# 5_-BUTTONS_ILLUMINATION.net
KiCad netlist of a schematic drawn in Altium Designer
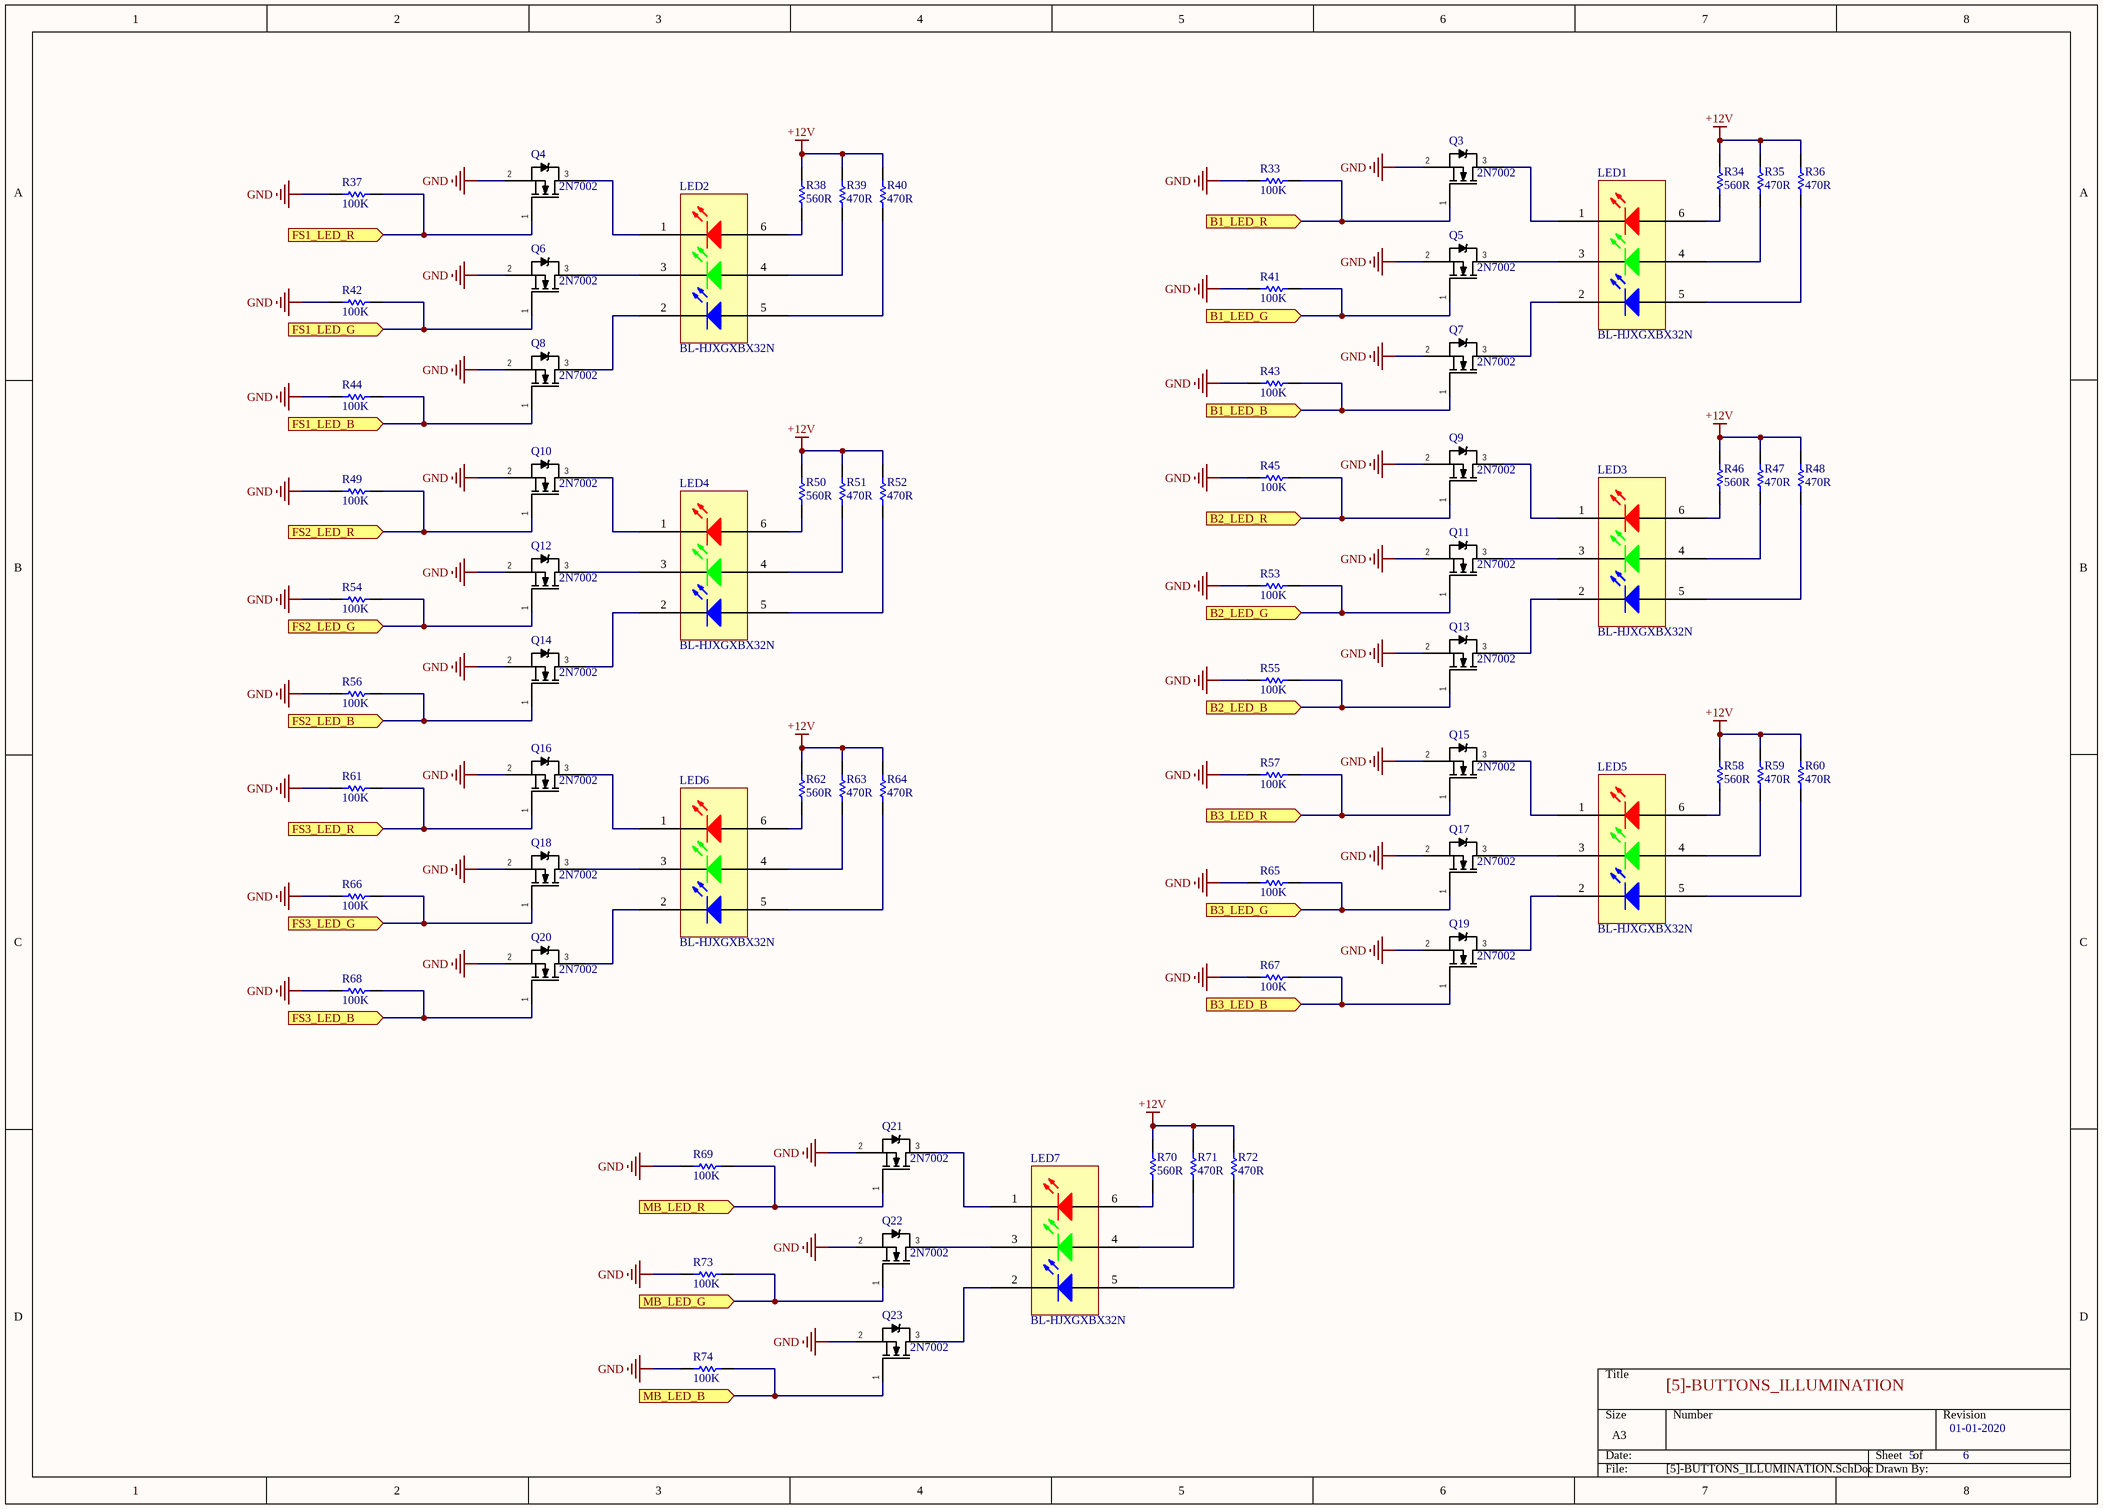
[diagram p0: [5]-BUTTONS_ILLUMINATION.SchDoc]

(export (version "E")
  (design (tool "Eeschema 10.0.6"))
  (components
    (comp (ref "LED1")
      (value "BL-HJXGXBX32N")
      (footprint "BL-HJXGXBX32N")
      (description "LED RGB 6PLCC SMD")
      (libsource (lib "bitsnio") (part "BL-HJXGXBX32N"))
    )
    (comp (ref "LED2")
      (value "BL-HJXGXBX32N")
      (footprint "BL-HJXGXBX32N")
      (description "LED RGB 6PLCC SMD")
      (libsource (lib "bitsnio") (part "BL-HJXGXBX32N"))
    )
    (comp (ref "LED3")
      (value "BL-HJXGXBX32N")
      (footprint "BL-HJXGXBX32N")
      (description "LED RGB 6PLCC SMD")
      (libsource (lib "bitsnio") (part "BL-HJXGXBX32N"))
    )
    (comp (ref "LED4")
      (value "BL-HJXGXBX32N")
      (footprint "BL-HJXGXBX32N")
      (description "LED RGB 6PLCC SMD")
      (libsource (lib "bitsnio") (part "BL-HJXGXBX32N"))
    )
    (comp (ref "LED5")
      (value "BL-HJXGXBX32N")
      (footprint "BL-HJXGXBX32N")
      (description "LED RGB 6PLCC SMD")
      (libsource (lib "bitsnio") (part "BL-HJXGXBX32N"))
    )
    (comp (ref "LED6")
      (value "BL-HJXGXBX32N")
      (footprint "BL-HJXGXBX32N")
      (description "LED RGB 6PLCC SMD")
      (libsource (lib "bitsnio") (part "BL-HJXGXBX32N"))
    )
    (comp (ref "LED7")
      (value "BL-HJXGXBX32N")
      (footprint "BL-HJXGXBX32N")
      (description "LED RGB 6PLCC SMD")
      (libsource (lib "bitsnio") (part "BL-HJXGXBX32N"))
    )
    (comp (ref "Q3")
      (value "2N7002")
      (footprint "SOT23-3N")
      (description "MOSFET N-CH 60V 115MA SOT-23")
      (fields (field (name "VOLTAGE") "60V"))
      (libsource (lib "bitsnio") (part "2N7002"))
    )
    (comp (ref "Q4")
      (value "2N7002")
      (footprint "SOT23-3N")
      (description "MOSFET N-CH 60V 115MA SOT-23")
      (fields (field (name "VOLTAGE") "60V"))
      (libsource (lib "bitsnio") (part "2N7002"))
    )
    (comp (ref "Q5")
      (value "2N7002")
      (footprint "SOT23-3N")
      (description "MOSFET N-CH 60V 115MA SOT-23")
      (fields (field (name "VOLTAGE") "60V"))
      (libsource (lib "bitsnio") (part "2N7002"))
    )
    (comp (ref "Q6")
      (value "2N7002")
      (footprint "SOT23-3N")
      (description "MOSFET N-CH 60V 115MA SOT-23")
      (fields (field (name "VOLTAGE") "60V"))
      (libsource (lib "bitsnio") (part "2N7002"))
    )
    (comp (ref "Q7")
      (value "2N7002")
      (footprint "SOT23-3N")
      (description "MOSFET N-CH 60V 115MA SOT-23")
      (fields (field (name "VOLTAGE") "60V"))
      (libsource (lib "bitsnio") (part "2N7002"))
    )
    (comp (ref "Q8")
      (value "2N7002")
      (footprint "SOT23-3N")
      (description "MOSFET N-CH 60V 115MA SOT-23")
      (fields (field (name "VOLTAGE") "60V"))
      (libsource (lib "bitsnio") (part "2N7002"))
    )
    (comp (ref "Q9")
      (value "2N7002")
      (footprint "SOT23-3N")
      (description "MOSFET N-CH 60V 115MA SOT-23")
      (fields (field (name "VOLTAGE") "60V"))
      (libsource (lib "bitsnio") (part "2N7002"))
    )
    (comp (ref "Q10")
      (value "2N7002")
      (footprint "SOT23-3N")
      (description "MOSFET N-CH 60V 115MA SOT-23")
      (fields (field (name "VOLTAGE") "60V"))
      (libsource (lib "bitsnio") (part "2N7002"))
    )
    (comp (ref "Q11")
      (value "2N7002")
      (footprint "SOT23-3N")
      (description "MOSFET N-CH 60V 115MA SOT-23")
      (fields (field (name "VOLTAGE") "60V"))
      (libsource (lib "bitsnio") (part "2N7002"))
    )
    (comp (ref "Q12")
      (value "2N7002")
      (footprint "SOT23-3N")
      (description "MOSFET N-CH 60V 115MA SOT-23")
      (fields (field (name "VOLTAGE") "60V"))
      (libsource (lib "bitsnio") (part "2N7002"))
    )
    (comp (ref "Q13")
      (value "2N7002")
      (footprint "SOT23-3N")
      (description "MOSFET N-CH 60V 115MA SOT-23")
      (fields (field (name "VOLTAGE") "60V"))
      (libsource (lib "bitsnio") (part "2N7002"))
    )
    (comp (ref "Q14")
      (value "2N7002")
      (footprint "SOT23-3N")
      (description "MOSFET N-CH 60V 115MA SOT-23")
      (fields (field (name "VOLTAGE") "60V"))
      (libsource (lib "bitsnio") (part "2N7002"))
    )
    (comp (ref "Q15")
      (value "2N7002")
      (footprint "SOT23-3N")
      (description "MOSFET N-CH 60V 115MA SOT-23")
      (fields (field (name "VOLTAGE") "60V"))
      (libsource (lib "bitsnio") (part "2N7002"))
    )
    (comp (ref "Q16")
      (value "2N7002")
      (footprint "SOT23-3N")
      (description "MOSFET N-CH 60V 115MA SOT-23")
      (fields (field (name "VOLTAGE") "60V"))
      (libsource (lib "bitsnio") (part "2N7002"))
    )
    (comp (ref "Q17")
      (value "2N7002")
      (footprint "SOT23-3N")
      (description "MOSFET N-CH 60V 115MA SOT-23")
      (fields (field (name "VOLTAGE") "60V"))
      (libsource (lib "bitsnio") (part "2N7002"))
    )
    (comp (ref "Q18")
      (value "2N7002")
      (footprint "SOT23-3N")
      (description "MOSFET N-CH 60V 115MA SOT-23")
      (fields (field (name "VOLTAGE") "60V"))
      (libsource (lib "bitsnio") (part "2N7002"))
    )
    (comp (ref "Q19")
      (value "2N7002")
      (footprint "SOT23-3N")
      (description "MOSFET N-CH 60V 115MA SOT-23")
      (fields (field (name "VOLTAGE") "60V"))
      (libsource (lib "bitsnio") (part "2N7002"))
    )
    (comp (ref "Q20")
      (value "2N7002")
      (footprint "SOT23-3N")
      (description "MOSFET N-CH 60V 115MA SOT-23")
      (fields (field (name "VOLTAGE") "60V"))
      (libsource (lib "bitsnio") (part "2N7002"))
    )
    (comp (ref "Q21")
      (value "2N7002")
      (footprint "SOT23-3N")
      (description "MOSFET N-CH 60V 115MA SOT-23")
      (fields (field (name "VOLTAGE") "60V"))
      (libsource (lib "bitsnio") (part "2N7002"))
    )
    (comp (ref "Q22")
      (value "2N7002")
      (footprint "SOT23-3N")
      (description "MOSFET N-CH 60V 115MA SOT-23")
      (fields (field (name "VOLTAGE") "60V"))
      (libsource (lib "bitsnio") (part "2N7002"))
    )
    (comp (ref "Q23")
      (value "2N7002")
      (footprint "SOT23-3N")
      (description "MOSFET N-CH 60V 115MA SOT-23")
      (fields (field (name "VOLTAGE") "60V"))
      (libsource (lib "bitsnio") (part "2N7002"))
    )
    (comp (ref "R33")
      (value "100K")
      (footprint "RESC1608N")
      (description "RES SMD 100K OHM 5% 1/4W 0603")
      (fields (field (name "TOLERANCE") "5%"))
      (libsource (lib "bitsnio") (part "ESR03EZPJ104"))
    )
    (comp (ref "R34")
      (value "560R")
      (footprint "RESC1608N")
      (description "RES SMD 560 OHM 5% 1/10W 0603")
      (fields (field (name "TOLERANCE") "5%"))
      (libsource (lib "bitsnio") (part "AC0603JR-07560RL"))
    )
    (comp (ref "R35")
      (value "470R")
      (footprint "RESC1608N")
      (description "RES SMD 470 OHM 5% 1/10W 0603")
      (fields (field (name "TOLERANCE") "5%"))
      (libsource (lib "bitsnio") (part "RMCF0603JT470R"))
    )
    (comp (ref "R36")
      (value "470R")
      (footprint "RESC1608N")
      (description "RES SMD 470 OHM 5% 1/10W 0603")
      (fields (field (name "TOLERANCE") "5%"))
      (libsource (lib "bitsnio") (part "RMCF0603JT470R"))
    )
    (comp (ref "R37")
      (value "100K")
      (footprint "RESC1608N")
      (description "RES SMD 100K OHM 5% 1/4W 0603")
      (fields (field (name "TOLERANCE") "5%"))
      (libsource (lib "bitsnio") (part "ESR03EZPJ104"))
    )
    (comp (ref "R38")
      (value "560R")
      (footprint "RESC1608N")
      (description "RES SMD 560 OHM 5% 1/10W 0603")
      (fields (field (name "TOLERANCE") "5%"))
      (libsource (lib "bitsnio") (part "AC0603JR-07560RL"))
    )
    (comp (ref "R39")
      (value "470R")
      (footprint "RESC1608N")
      (description "RES SMD 470 OHM 5% 1/10W 0603")
      (fields (field (name "TOLERANCE") "5%"))
      (libsource (lib "bitsnio") (part "RMCF0603JT470R"))
    )
    (comp (ref "R40")
      (value "470R")
      (footprint "RESC1608N")
      (description "RES SMD 470 OHM 5% 1/10W 0603")
      (fields (field (name "TOLERANCE") "5%"))
      (libsource (lib "bitsnio") (part "RMCF0603JT470R"))
    )
    (comp (ref "R41")
      (value "100K")
      (footprint "RESC1608N")
      (description "RES SMD 100K OHM 5% 1/4W 0603")
      (fields (field (name "TOLERANCE") "5%"))
      (libsource (lib "bitsnio") (part "ESR03EZPJ104"))
    )
    (comp (ref "R42")
      (value "100K")
      (footprint "RESC1608N")
      (description "RES SMD 100K OHM 5% 1/4W 0603")
      (fields (field (name "TOLERANCE") "5%"))
      (libsource (lib "bitsnio") (part "ESR03EZPJ104"))
    )
    (comp (ref "R43")
      (value "100K")
      (footprint "RESC1608N")
      (description "RES SMD 100K OHM 5% 1/4W 0603")
      (fields (field (name "TOLERANCE") "5%"))
      (libsource (lib "bitsnio") (part "ESR03EZPJ104"))
    )
    (comp (ref "R44")
      (value "100K")
      (footprint "RESC1608N")
      (description "RES SMD 100K OHM 5% 1/4W 0603")
      (fields (field (name "TOLERANCE") "5%"))
      (libsource (lib "bitsnio") (part "ESR03EZPJ104"))
    )
    (comp (ref "R45")
      (value "100K")
      (footprint "RESC1608N")
      (description "RES SMD 100K OHM 5% 1/4W 0603")
      (fields (field (name "TOLERANCE") "5%"))
      (libsource (lib "bitsnio") (part "ESR03EZPJ104"))
    )
    (comp (ref "R46")
      (value "560R")
      (footprint "RESC1608N")
      (description "RES SMD 560 OHM 5% 1/10W 0603")
      (fields (field (name "TOLERANCE") "5%"))
      (libsource (lib "bitsnio") (part "AC0603JR-07560RL"))
    )
    (comp (ref "R47")
      (value "470R")
      (footprint "RESC1608N")
      (description "RES SMD 470 OHM 5% 1/10W 0603")
      (fields (field (name "TOLERANCE") "5%"))
      (libsource (lib "bitsnio") (part "RMCF0603JT470R"))
    )
    (comp (ref "R48")
      (value "470R")
      (footprint "RESC1608N")
      (description "RES SMD 470 OHM 5% 1/10W 0603")
      (fields (field (name "TOLERANCE") "5%"))
      (libsource (lib "bitsnio") (part "RMCF0603JT470R"))
    )
    (comp (ref "R49")
      (value "100K")
      (footprint "RESC1608N")
      (description "RES SMD 100K OHM 5% 1/4W 0603")
      (fields (field (name "TOLERANCE") "5%"))
      (libsource (lib "bitsnio") (part "ESR03EZPJ104"))
    )
    (comp (ref "R50")
      (value "560R")
      (footprint "RESC1608N")
      (description "RES SMD 560 OHM 5% 1/10W 0603")
      (fields (field (name "TOLERANCE") "5%"))
      (libsource (lib "bitsnio") (part "AC0603JR-07560RL"))
    )
    (comp (ref "R51")
      (value "470R")
      (footprint "RESC1608N")
      (description "RES SMD 470 OHM 5% 1/10W 0603")
      (fields (field (name "TOLERANCE") "5%"))
      (libsource (lib "bitsnio") (part "RMCF0603JT470R"))
    )
    (comp (ref "R52")
      (value "470R")
      (footprint "RESC1608N")
      (description "RES SMD 470 OHM 5% 1/10W 0603")
      (fields (field (name "TOLERANCE") "5%"))
      (libsource (lib "bitsnio") (part "RMCF0603JT470R"))
    )
    (comp (ref "R53")
      (value "100K")
      (footprint "RESC1608N")
      (description "RES SMD 100K OHM 5% 1/4W 0603")
      (fields (field (name "TOLERANCE") "5%"))
      (libsource (lib "bitsnio") (part "ESR03EZPJ104"))
    )
    (comp (ref "R54")
      (value "100K")
      (footprint "RESC1608N")
      (description "RES SMD 100K OHM 5% 1/4W 0603")
      (fields (field (name "TOLERANCE") "5%"))
      (libsource (lib "bitsnio") (part "ESR03EZPJ104"))
    )
    (comp (ref "R55")
      (value "100K")
      (footprint "RESC1608N")
      (description "RES SMD 100K OHM 5% 1/4W 0603")
      (fields (field (name "TOLERANCE") "5%"))
      (libsource (lib "bitsnio") (part "ESR03EZPJ104"))
    )
    (comp (ref "R56")
      (value "100K")
      (footprint "RESC1608N")
      (description "RES SMD 100K OHM 5% 1/4W 0603")
      (fields (field (name "TOLERANCE") "5%"))
      (libsource (lib "bitsnio") (part "ESR03EZPJ104"))
    )
    (comp (ref "R57")
      (value "100K")
      (footprint "RESC1608N")
      (description "RES SMD 100K OHM 5% 1/4W 0603")
      (fields (field (name "TOLERANCE") "5%"))
      (libsource (lib "bitsnio") (part "ESR03EZPJ104"))
    )
    (comp (ref "R58")
      (value "560R")
      (footprint "RESC1608N")
      (description "RES SMD 560 OHM 5% 1/10W 0603")
      (fields (field (name "TOLERANCE") "5%"))
      (libsource (lib "bitsnio") (part "AC0603JR-07560RL"))
    )
    (comp (ref "R59")
      (value "470R")
      (footprint "RESC1608N")
      (description "RES SMD 470 OHM 5% 1/10W 0603")
      (fields (field (name "TOLERANCE") "5%"))
      (libsource (lib "bitsnio") (part "RMCF0603JT470R"))
    )
    (comp (ref "R60")
      (value "470R")
      (footprint "RESC1608N")
      (description "RES SMD 470 OHM 5% 1/10W 0603")
      (fields (field (name "TOLERANCE") "5%"))
      (libsource (lib "bitsnio") (part "RMCF0603JT470R"))
    )
    (comp (ref "R61")
      (value "100K")
      (footprint "RESC1608N")
      (description "RES SMD 100K OHM 5% 1/4W 0603")
      (fields (field (name "TOLERANCE") "5%"))
      (libsource (lib "bitsnio") (part "ESR03EZPJ104"))
    )
    (comp (ref "R62")
      (value "560R")
      (footprint "RESC1608N")
      (description "RES SMD 560 OHM 5% 1/10W 0603")
      (fields (field (name "TOLERANCE") "5%"))
      (libsource (lib "bitsnio") (part "AC0603JR-07560RL"))
    )
    (comp (ref "R63")
      (value "470R")
      (footprint "RESC1608N")
      (description "RES SMD 470 OHM 5% 1/10W 0603")
      (fields (field (name "TOLERANCE") "5%"))
      (libsource (lib "bitsnio") (part "RMCF0603JT470R"))
    )
    (comp (ref "R64")
      (value "470R")
      (footprint "RESC1608N")
      (description "RES SMD 470 OHM 5% 1/10W 0603")
      (fields (field (name "TOLERANCE") "5%"))
      (libsource (lib "bitsnio") (part "RMCF0603JT470R"))
    )
    (comp (ref "R65")
      (value "100K")
      (footprint "RESC1608N")
      (description "RES SMD 100K OHM 5% 1/4W 0603")
      (fields (field (name "TOLERANCE") "5%"))
      (libsource (lib "bitsnio") (part "ESR03EZPJ104"))
    )
    (comp (ref "R66")
      (value "100K")
      (footprint "RESC1608N")
      (description "RES SMD 100K OHM 5% 1/4W 0603")
      (fields (field (name "TOLERANCE") "5%"))
      (libsource (lib "bitsnio") (part "ESR03EZPJ104"))
    )
    (comp (ref "R67")
      (value "100K")
      (footprint "RESC1608N")
      (description "RES SMD 100K OHM 5% 1/4W 0603")
      (fields (field (name "TOLERANCE") "5%"))
      (libsource (lib "bitsnio") (part "ESR03EZPJ104"))
    )
    (comp (ref "R68")
      (value "100K")
      (footprint "RESC1608N")
      (description "RES SMD 100K OHM 5% 1/4W 0603")
      (fields (field (name "TOLERANCE") "5%"))
      (libsource (lib "bitsnio") (part "ESR03EZPJ104"))
    )
    (comp (ref "R69")
      (value "100K")
      (footprint "RESC1608N")
      (description "RES SMD 100K OHM 5% 1/4W 0603")
      (fields (field (name "TOLERANCE") "5%"))
      (libsource (lib "bitsnio") (part "ESR03EZPJ104"))
    )
    (comp (ref "R70")
      (value "560R")
      (footprint "RESC1608N")
      (description "RES SMD 560 OHM 5% 1/10W 0603")
      (fields (field (name "TOLERANCE") "5%"))
      (libsource (lib "bitsnio") (part "AC0603JR-07560RL"))
    )
    (comp (ref "R71")
      (value "470R")
      (footprint "RESC1608N")
      (description "RES SMD 470 OHM 5% 1/10W 0603")
      (fields (field (name "TOLERANCE") "5%"))
      (libsource (lib "bitsnio") (part "RMCF0603JT470R"))
    )
    (comp (ref "R72")
      (value "470R")
      (footprint "RESC1608N")
      (description "RES SMD 470 OHM 5% 1/10W 0603")
      (fields (field (name "TOLERANCE") "5%"))
      (libsource (lib "bitsnio") (part "RMCF0603JT470R"))
    )
    (comp (ref "R73")
      (value "100K")
      (footprint "RESC1608N")
      (description "RES SMD 100K OHM 5% 1/4W 0603")
      (fields (field (name "TOLERANCE") "5%"))
      (libsource (lib "bitsnio") (part "ESR03EZPJ104"))
    )
    (comp (ref "R74")
      (value "100K")
      (footprint "RESC1608N")
      (description "RES SMD 100K OHM 5% 1/4W 0603")
      (fields (field (name "TOLERANCE") "5%"))
      (libsource (lib "bitsnio") (part "ESR03EZPJ104"))
    )
  )
  (nets
    (net (code "1") (name "+12V") (class "Default")
      (node (ref "R34") (pin "2") (pinfunction "2_2") (pintype "passive"))
      (node (ref "R35") (pin "2") (pinfunction "2_2") (pintype "passive"))
      (node (ref "R36") (pin "2") (pinfunction "2_2") (pintype "passive"))
      (node (ref "R38") (pin "2") (pinfunction "2_2") (pintype "passive"))
      (node (ref "R39") (pin "2") (pinfunction "2_2") (pintype "passive"))
      (node (ref "R40") (pin "2") (pinfunction "2_2") (pintype "passive"))
      (node (ref "R46") (pin "2") (pinfunction "2_2") (pintype "passive"))
      (node (ref "R47") (pin "2") (pinfunction "2_2") (pintype "passive"))
      (node (ref "R48") (pin "2") (pinfunction "2_2") (pintype "passive"))
      (node (ref "R50") (pin "2") (pinfunction "2_2") (pintype "passive"))
      (node (ref "R51") (pin "2") (pinfunction "2_2") (pintype "passive"))
      (node (ref "R52") (pin "2") (pinfunction "2_2") (pintype "passive"))
      (node (ref "R58") (pin "2") (pinfunction "2_2") (pintype "passive"))
      (node (ref "R59") (pin "2") (pinfunction "2_2") (pintype "passive"))
      (node (ref "R60") (pin "2") (pinfunction "2_2") (pintype "passive"))
      (node (ref "R62") (pin "2") (pinfunction "2_2") (pintype "passive"))
      (node (ref "R63") (pin "2") (pinfunction "2_2") (pintype "passive"))
      (node (ref "R64") (pin "2") (pinfunction "2_2") (pintype "passive"))
      (node (ref "R70") (pin "2") (pinfunction "2_2") (pintype "passive"))
      (node (ref "R71") (pin "2") (pinfunction "2_2") (pintype "passive"))
      (node (ref "R72") (pin "2") (pinfunction "2_2") (pintype "passive"))
    )
    (net (code "2") (name "/B1_LED_B") (class "Default")
      (node (ref "Q7") (pin "1") (pinfunction "G_1") (pintype "passive"))
      (node (ref "R43") (pin "1") (pinfunction "1_1") (pintype "passive"))
    )
    (net (code "3") (name "/B1_LED_G") (class "Default")
      (node (ref "Q5") (pin "1") (pinfunction "G_1") (pintype "passive"))
      (node (ref "R41") (pin "1") (pinfunction "1_1") (pintype "passive"))
    )
    (net (code "4") (name "/B1_LED_R") (class "Default")
      (node (ref "Q3") (pin "1") (pinfunction "G_1") (pintype "passive"))
      (node (ref "R33") (pin "1") (pinfunction "1_1") (pintype "passive"))
    )
    (net (code "5") (name "/B2_LED_B") (class "Default")
      (node (ref "Q13") (pin "1") (pinfunction "G_1") (pintype "passive"))
      (node (ref "R55") (pin "1") (pinfunction "1_1") (pintype "passive"))
    )
    (net (code "6") (name "/B2_LED_G") (class "Default")
      (node (ref "Q11") (pin "1") (pinfunction "G_1") (pintype "passive"))
      (node (ref "R53") (pin "1") (pinfunction "1_1") (pintype "passive"))
    )
    (net (code "7") (name "/B2_LED_R") (class "Default")
      (node (ref "Q9") (pin "1") (pinfunction "G_1") (pintype "passive"))
      (node (ref "R45") (pin "1") (pinfunction "1_1") (pintype "passive"))
    )
    (net (code "8") (name "/B3_LED_B") (class "Default")
      (node (ref "Q19") (pin "1") (pinfunction "G_1") (pintype "passive"))
      (node (ref "R67") (pin "1") (pinfunction "1_1") (pintype "passive"))
    )
    (net (code "9") (name "/B3_LED_G") (class "Default")
      (node (ref "Q17") (pin "1") (pinfunction "G_1") (pintype "passive"))
      (node (ref "R65") (pin "1") (pinfunction "1_1") (pintype "passive"))
    )
    (net (code "10") (name "/B3_LED_R") (class "Default")
      (node (ref "Q15") (pin "1") (pinfunction "G_1") (pintype "passive"))
      (node (ref "R57") (pin "1") (pinfunction "1_1") (pintype "passive"))
    )
    (net (code "11") (name "/FS1_LED_B") (class "Default")
      (node (ref "Q8") (pin "1") (pinfunction "G_1") (pintype "passive"))
      (node (ref "R44") (pin "1") (pinfunction "1_1") (pintype "passive"))
    )
    (net (code "12") (name "/FS1_LED_G") (class "Default")
      (node (ref "Q6") (pin "1") (pinfunction "G_1") (pintype "passive"))
      (node (ref "R42") (pin "1") (pinfunction "1_1") (pintype "passive"))
    )
    (net (code "13") (name "/FS1_LED_R") (class "Default")
      (node (ref "Q4") (pin "1") (pinfunction "G_1") (pintype "passive"))
      (node (ref "R37") (pin "1") (pinfunction "1_1") (pintype "passive"))
    )
    (net (code "14") (name "/FS2_LED_B") (class "Default")
      (node (ref "Q14") (pin "1") (pinfunction "G_1") (pintype "passive"))
      (node (ref "R56") (pin "1") (pinfunction "1_1") (pintype "passive"))
    )
    (net (code "15") (name "/FS2_LED_G") (class "Default")
      (node (ref "Q12") (pin "1") (pinfunction "G_1") (pintype "passive"))
      (node (ref "R54") (pin "1") (pinfunction "1_1") (pintype "passive"))
    )
    (net (code "16") (name "/FS2_LED_R") (class "Default")
      (node (ref "Q10") (pin "1") (pinfunction "G_1") (pintype "passive"))
      (node (ref "R49") (pin "1") (pinfunction "1_1") (pintype "passive"))
    )
    (net (code "17") (name "/FS3_LED_B") (class "Default")
      (node (ref "Q20") (pin "1") (pinfunction "G_1") (pintype "passive"))
      (node (ref "R68") (pin "1") (pinfunction "1_1") (pintype "passive"))
    )
    (net (code "18") (name "/FS3_LED_G") (class "Default")
      (node (ref "Q18") (pin "1") (pinfunction "G_1") (pintype "passive"))
      (node (ref "R66") (pin "1") (pinfunction "1_1") (pintype "passive"))
    )
    (net (code "19") (name "/FS3_LED_R") (class "Default")
      (node (ref "Q16") (pin "1") (pinfunction "G_1") (pintype "passive"))
      (node (ref "R61") (pin "1") (pinfunction "1_1") (pintype "passive"))
    )
    (net (code "20") (name "/MB_LED_B") (class "Default")
      (node (ref "Q23") (pin "1") (pinfunction "G_1") (pintype "passive"))
      (node (ref "R74") (pin "1") (pinfunction "1_1") (pintype "passive"))
    )
    (net (code "21") (name "/MB_LED_G") (class "Default")
      (node (ref "Q22") (pin "1") (pinfunction "G_1") (pintype "passive"))
      (node (ref "R73") (pin "1") (pinfunction "1_1") (pintype "passive"))
    )
    (net (code "22") (name "/MB_LED_R") (class "Default")
      (node (ref "Q21") (pin "1") (pinfunction "G_1") (pintype "passive"))
      (node (ref "R69") (pin "1") (pinfunction "1_1") (pintype "passive"))
    )
    (net (code "23") (name "GND") (class "Default")
      (node (ref "Q10") (pin "2") (pinfunction "S_2") (pintype "passive"))
      (node (ref "Q11") (pin "2") (pinfunction "S_2") (pintype "passive"))
      (node (ref "Q12") (pin "2") (pinfunction "S_2") (pintype "passive"))
      (node (ref "Q13") (pin "2") (pinfunction "S_2") (pintype "passive"))
      (node (ref "Q14") (pin "2") (pinfunction "S_2") (pintype "passive"))
      (node (ref "Q15") (pin "2") (pinfunction "S_2") (pintype "passive"))
      (node (ref "Q16") (pin "2") (pinfunction "S_2") (pintype "passive"))
      (node (ref "Q17") (pin "2") (pinfunction "S_2") (pintype "passive"))
      (node (ref "Q18") (pin "2") (pinfunction "S_2") (pintype "passive"))
      (node (ref "Q19") (pin "2") (pinfunction "S_2") (pintype "passive"))
      (node (ref "Q20") (pin "2") (pinfunction "S_2") (pintype "passive"))
      (node (ref "Q21") (pin "2") (pinfunction "S_2") (pintype "passive"))
      (node (ref "Q22") (pin "2") (pinfunction "S_2") (pintype "passive"))
      (node (ref "Q23") (pin "2") (pinfunction "S_2") (pintype "passive"))
      (node (ref "Q3") (pin "2") (pinfunction "S_2") (pintype "passive"))
      (node (ref "Q4") (pin "2") (pinfunction "S_2") (pintype "passive"))
      (node (ref "Q5") (pin "2") (pinfunction "S_2") (pintype "passive"))
      (node (ref "Q6") (pin "2") (pinfunction "S_2") (pintype "passive"))
      (node (ref "Q7") (pin "2") (pinfunction "S_2") (pintype "passive"))
      (node (ref "Q8") (pin "2") (pinfunction "S_2") (pintype "passive"))
      (node (ref "Q9") (pin "2") (pinfunction "S_2") (pintype "passive"))
      (node (ref "R33") (pin "2") (pinfunction "2_2") (pintype "passive"))
      (node (ref "R37") (pin "2") (pinfunction "2_2") (pintype "passive"))
      (node (ref "R41") (pin "2") (pinfunction "2_2") (pintype "passive"))
      (node (ref "R42") (pin "2") (pinfunction "2_2") (pintype "passive"))
      (node (ref "R43") (pin "2") (pinfunction "2_2") (pintype "passive"))
      (node (ref "R44") (pin "2") (pinfunction "2_2") (pintype "passive"))
      (node (ref "R45") (pin "2") (pinfunction "2_2") (pintype "passive"))
      (node (ref "R49") (pin "2") (pinfunction "2_2") (pintype "passive"))
      (node (ref "R53") (pin "2") (pinfunction "2_2") (pintype "passive"))
      (node (ref "R54") (pin "2") (pinfunction "2_2") (pintype "passive"))
      (node (ref "R55") (pin "2") (pinfunction "2_2") (pintype "passive"))
      (node (ref "R56") (pin "2") (pinfunction "2_2") (pintype "passive"))
      (node (ref "R57") (pin "2") (pinfunction "2_2") (pintype "passive"))
      (node (ref "R61") (pin "2") (pinfunction "2_2") (pintype "passive"))
      (node (ref "R65") (pin "2") (pinfunction "2_2") (pintype "passive"))
      (node (ref "R66") (pin "2") (pinfunction "2_2") (pintype "passive"))
      (node (ref "R67") (pin "2") (pinfunction "2_2") (pintype "passive"))
      (node (ref "R68") (pin "2") (pinfunction "2_2") (pintype "passive"))
      (node (ref "R69") (pin "2") (pinfunction "2_2") (pintype "passive"))
      (node (ref "R73") (pin "2") (pinfunction "2_2") (pintype "passive"))
      (node (ref "R74") (pin "2") (pinfunction "2_2") (pintype "passive"))
    )
    (net (code "24") (name "Net-(LED1-Pad4)") (class "Default")
      (node (ref "LED1") (pin "4") (pinfunction "4_4") (pintype "passive"))
      (node (ref "R35") (pin "1") (pinfunction "1_1") (pintype "passive"))
    )
    (net (code "25") (name "Net-(LED1-Pad5)") (class "Default")
      (node (ref "LED1") (pin "5") (pinfunction "5_5") (pintype "passive"))
      (node (ref "R36") (pin "1") (pinfunction "1_1") (pintype "passive"))
    )
    (net (code "26") (name "Net-(LED1-Pad6)") (class "Default")
      (node (ref "LED1") (pin "6") (pinfunction "6_6") (pintype "passive"))
      (node (ref "R34") (pin "1") (pinfunction "1_1") (pintype "passive"))
    )
    (net (code "27") (name "Net-(LED2-Pad4)") (class "Default")
      (node (ref "LED2") (pin "4") (pinfunction "4_4") (pintype "passive"))
      (node (ref "R39") (pin "1") (pinfunction "1_1") (pintype "passive"))
    )
    (net (code "28") (name "Net-(LED2-Pad5)") (class "Default")
      (node (ref "LED2") (pin "5") (pinfunction "5_5") (pintype "passive"))
      (node (ref "R40") (pin "1") (pinfunction "1_1") (pintype "passive"))
    )
    (net (code "29") (name "Net-(LED2-Pad6)") (class "Default")
      (node (ref "LED2") (pin "6") (pinfunction "6_6") (pintype "passive"))
      (node (ref "R38") (pin "1") (pinfunction "1_1") (pintype "passive"))
    )
    (net (code "30") (name "Net-(LED3-Pad4)") (class "Default")
      (node (ref "LED3") (pin "4") (pinfunction "4_4") (pintype "passive"))
      (node (ref "R47") (pin "1") (pinfunction "1_1") (pintype "passive"))
    )
    (net (code "31") (name "Net-(LED3-Pad5)") (class "Default")
      (node (ref "LED3") (pin "5") (pinfunction "5_5") (pintype "passive"))
      (node (ref "R48") (pin "1") (pinfunction "1_1") (pintype "passive"))
    )
    (net (code "32") (name "Net-(LED3-Pad6)") (class "Default")
      (node (ref "LED3") (pin "6") (pinfunction "6_6") (pintype "passive"))
      (node (ref "R46") (pin "1") (pinfunction "1_1") (pintype "passive"))
    )
    (net (code "33") (name "Net-(LED4-Pad4)") (class "Default")
      (node (ref "LED4") (pin "4") (pinfunction "4_4") (pintype "passive"))
      (node (ref "R51") (pin "1") (pinfunction "1_1") (pintype "passive"))
    )
    (net (code "34") (name "Net-(LED4-Pad5)") (class "Default")
      (node (ref "LED4") (pin "5") (pinfunction "5_5") (pintype "passive"))
      (node (ref "R52") (pin "1") (pinfunction "1_1") (pintype "passive"))
    )
    (net (code "35") (name "Net-(LED4-Pad6)") (class "Default")
      (node (ref "LED4") (pin "6") (pinfunction "6_6") (pintype "passive"))
      (node (ref "R50") (pin "1") (pinfunction "1_1") (pintype "passive"))
    )
    (net (code "36") (name "Net-(LED5-Pad4)") (class "Default")
      (node (ref "LED5") (pin "4") (pinfunction "4_4") (pintype "passive"))
      (node (ref "R59") (pin "1") (pinfunction "1_1") (pintype "passive"))
    )
    (net (code "37") (name "Net-(LED5-Pad5)") (class "Default")
      (node (ref "LED5") (pin "5") (pinfunction "5_5") (pintype "passive"))
      (node (ref "R60") (pin "1") (pinfunction "1_1") (pintype "passive"))
    )
    (net (code "38") (name "Net-(LED5-Pad6)") (class "Default")
      (node (ref "LED5") (pin "6") (pinfunction "6_6") (pintype "passive"))
      (node (ref "R58") (pin "1") (pinfunction "1_1") (pintype "passive"))
    )
    (net (code "39") (name "Net-(LED6-Pad4)") (class "Default")
      (node (ref "LED6") (pin "4") (pinfunction "4_4") (pintype "passive"))
      (node (ref "R63") (pin "1") (pinfunction "1_1") (pintype "passive"))
    )
    (net (code "40") (name "Net-(LED6-Pad5)") (class "Default")
      (node (ref "LED6") (pin "5") (pinfunction "5_5") (pintype "passive"))
      (node (ref "R64") (pin "1") (pinfunction "1_1") (pintype "passive"))
    )
    (net (code "41") (name "Net-(LED6-Pad6)") (class "Default")
      (node (ref "LED6") (pin "6") (pinfunction "6_6") (pintype "passive"))
      (node (ref "R62") (pin "1") (pinfunction "1_1") (pintype "passive"))
    )
    (net (code "42") (name "Net-(LED7-Pad4)") (class "Default")
      (node (ref "LED7") (pin "4") (pinfunction "4_4") (pintype "passive"))
      (node (ref "R71") (pin "1") (pinfunction "1_1") (pintype "passive"))
    )
    (net (code "43") (name "Net-(LED7-Pad5)") (class "Default")
      (node (ref "LED7") (pin "5") (pinfunction "5_5") (pintype "passive"))
      (node (ref "R72") (pin "1") (pinfunction "1_1") (pintype "passive"))
    )
    (net (code "44") (name "Net-(LED7-Pad6)") (class "Default")
      (node (ref "LED7") (pin "6") (pinfunction "6_6") (pintype "passive"))
      (node (ref "R70") (pin "1") (pinfunction "1_1") (pintype "passive"))
    )
    (net (code "45") (name "Net-(Q3-D)") (class "Default")
      (node (ref "LED1") (pin "1") (pinfunction "1_1") (pintype "passive"))
      (node (ref "Q3") (pin "3") (pinfunction "D_3") (pintype "passive"))
    )
    (net (code "46") (name "Net-(Q4-D)") (class "Default")
      (node (ref "LED2") (pin "1") (pinfunction "1_1") (pintype "passive"))
      (node (ref "Q4") (pin "3") (pinfunction "D_3") (pintype "passive"))
    )
    (net (code "47") (name "Net-(Q5-D)") (class "Default")
      (node (ref "LED1") (pin "3") (pinfunction "3_3") (pintype "passive"))
      (node (ref "Q5") (pin "3") (pinfunction "D_3") (pintype "passive"))
    )
    (net (code "48") (name "Net-(Q6-D)") (class "Default")
      (node (ref "LED2") (pin "3") (pinfunction "3_3") (pintype "passive"))
      (node (ref "Q6") (pin "3") (pinfunction "D_3") (pintype "passive"))
    )
    (net (code "49") (name "Net-(Q7-D)") (class "Default")
      (node (ref "LED1") (pin "2") (pinfunction "2_2") (pintype "passive"))
      (node (ref "Q7") (pin "3") (pinfunction "D_3") (pintype "passive"))
    )
    (net (code "50") (name "Net-(Q8-D)") (class "Default")
      (node (ref "LED2") (pin "2") (pinfunction "2_2") (pintype "passive"))
      (node (ref "Q8") (pin "3") (pinfunction "D_3") (pintype "passive"))
    )
    (net (code "51") (name "Net-(Q9-D)") (class "Default")
      (node (ref "LED3") (pin "1") (pinfunction "1_1") (pintype "passive"))
      (node (ref "Q9") (pin "3") (pinfunction "D_3") (pintype "passive"))
    )
    (net (code "52") (name "Net-(Q10-D)") (class "Default")
      (node (ref "LED4") (pin "1") (pinfunction "1_1") (pintype "passive"))
      (node (ref "Q10") (pin "3") (pinfunction "D_3") (pintype "passive"))
    )
    (net (code "53") (name "Net-(Q11-D)") (class "Default")
      (node (ref "LED3") (pin "3") (pinfunction "3_3") (pintype "passive"))
      (node (ref "Q11") (pin "3") (pinfunction "D_3") (pintype "passive"))
    )
    (net (code "54") (name "Net-(Q12-D)") (class "Default")
      (node (ref "LED4") (pin "3") (pinfunction "3_3") (pintype "passive"))
      (node (ref "Q12") (pin "3") (pinfunction "D_3") (pintype "passive"))
    )
    (net (code "55") (name "Net-(Q13-D)") (class "Default")
      (node (ref "LED3") (pin "2") (pinfunction "2_2") (pintype "passive"))
      (node (ref "Q13") (pin "3") (pinfunction "D_3") (pintype "passive"))
    )
    (net (code "56") (name "Net-(Q14-D)") (class "Default")
      (node (ref "LED4") (pin "2") (pinfunction "2_2") (pintype "passive"))
      (node (ref "Q14") (pin "3") (pinfunction "D_3") (pintype "passive"))
    )
    (net (code "57") (name "Net-(Q15-D)") (class "Default")
      (node (ref "LED5") (pin "1") (pinfunction "1_1") (pintype "passive"))
      (node (ref "Q15") (pin "3") (pinfunction "D_3") (pintype "passive"))
    )
    (net (code "58") (name "Net-(Q16-D)") (class "Default")
      (node (ref "LED6") (pin "1") (pinfunction "1_1") (pintype "passive"))
      (node (ref "Q16") (pin "3") (pinfunction "D_3") (pintype "passive"))
    )
    (net (code "59") (name "Net-(Q17-D)") (class "Default")
      (node (ref "LED5") (pin "3") (pinfunction "3_3") (pintype "passive"))
      (node (ref "Q17") (pin "3") (pinfunction "D_3") (pintype "passive"))
    )
    (net (code "60") (name "Net-(Q18-D)") (class "Default")
      (node (ref "LED6") (pin "3") (pinfunction "3_3") (pintype "passive"))
      (node (ref "Q18") (pin "3") (pinfunction "D_3") (pintype "passive"))
    )
    (net (code "61") (name "Net-(Q19-D)") (class "Default")
      (node (ref "LED5") (pin "2") (pinfunction "2_2") (pintype "passive"))
      (node (ref "Q19") (pin "3") (pinfunction "D_3") (pintype "passive"))
    )
    (net (code "62") (name "Net-(Q20-D)") (class "Default")
      (node (ref "LED6") (pin "2") (pinfunction "2_2") (pintype "passive"))
      (node (ref "Q20") (pin "3") (pinfunction "D_3") (pintype "passive"))
    )
    (net (code "63") (name "Net-(Q21-D)") (class "Default")
      (node (ref "LED7") (pin "1") (pinfunction "1_1") (pintype "passive"))
      (node (ref "Q21") (pin "3") (pinfunction "D_3") (pintype "passive"))
    )
    (net (code "64") (name "Net-(Q22-D)") (class "Default")
      (node (ref "LED7") (pin "3") (pinfunction "3_3") (pintype "passive"))
      (node (ref "Q22") (pin "3") (pinfunction "D_3") (pintype "passive"))
    )
    (net (code "65") (name "Net-(Q23-D)") (class "Default")
      (node (ref "LED7") (pin "2") (pinfunction "2_2") (pintype "passive"))
      (node (ref "Q23") (pin "3") (pinfunction "D_3") (pintype "passive"))
    )
  )
)
